# HP85disk.net
KiCad netlist of a schematic drawn in EAGLE
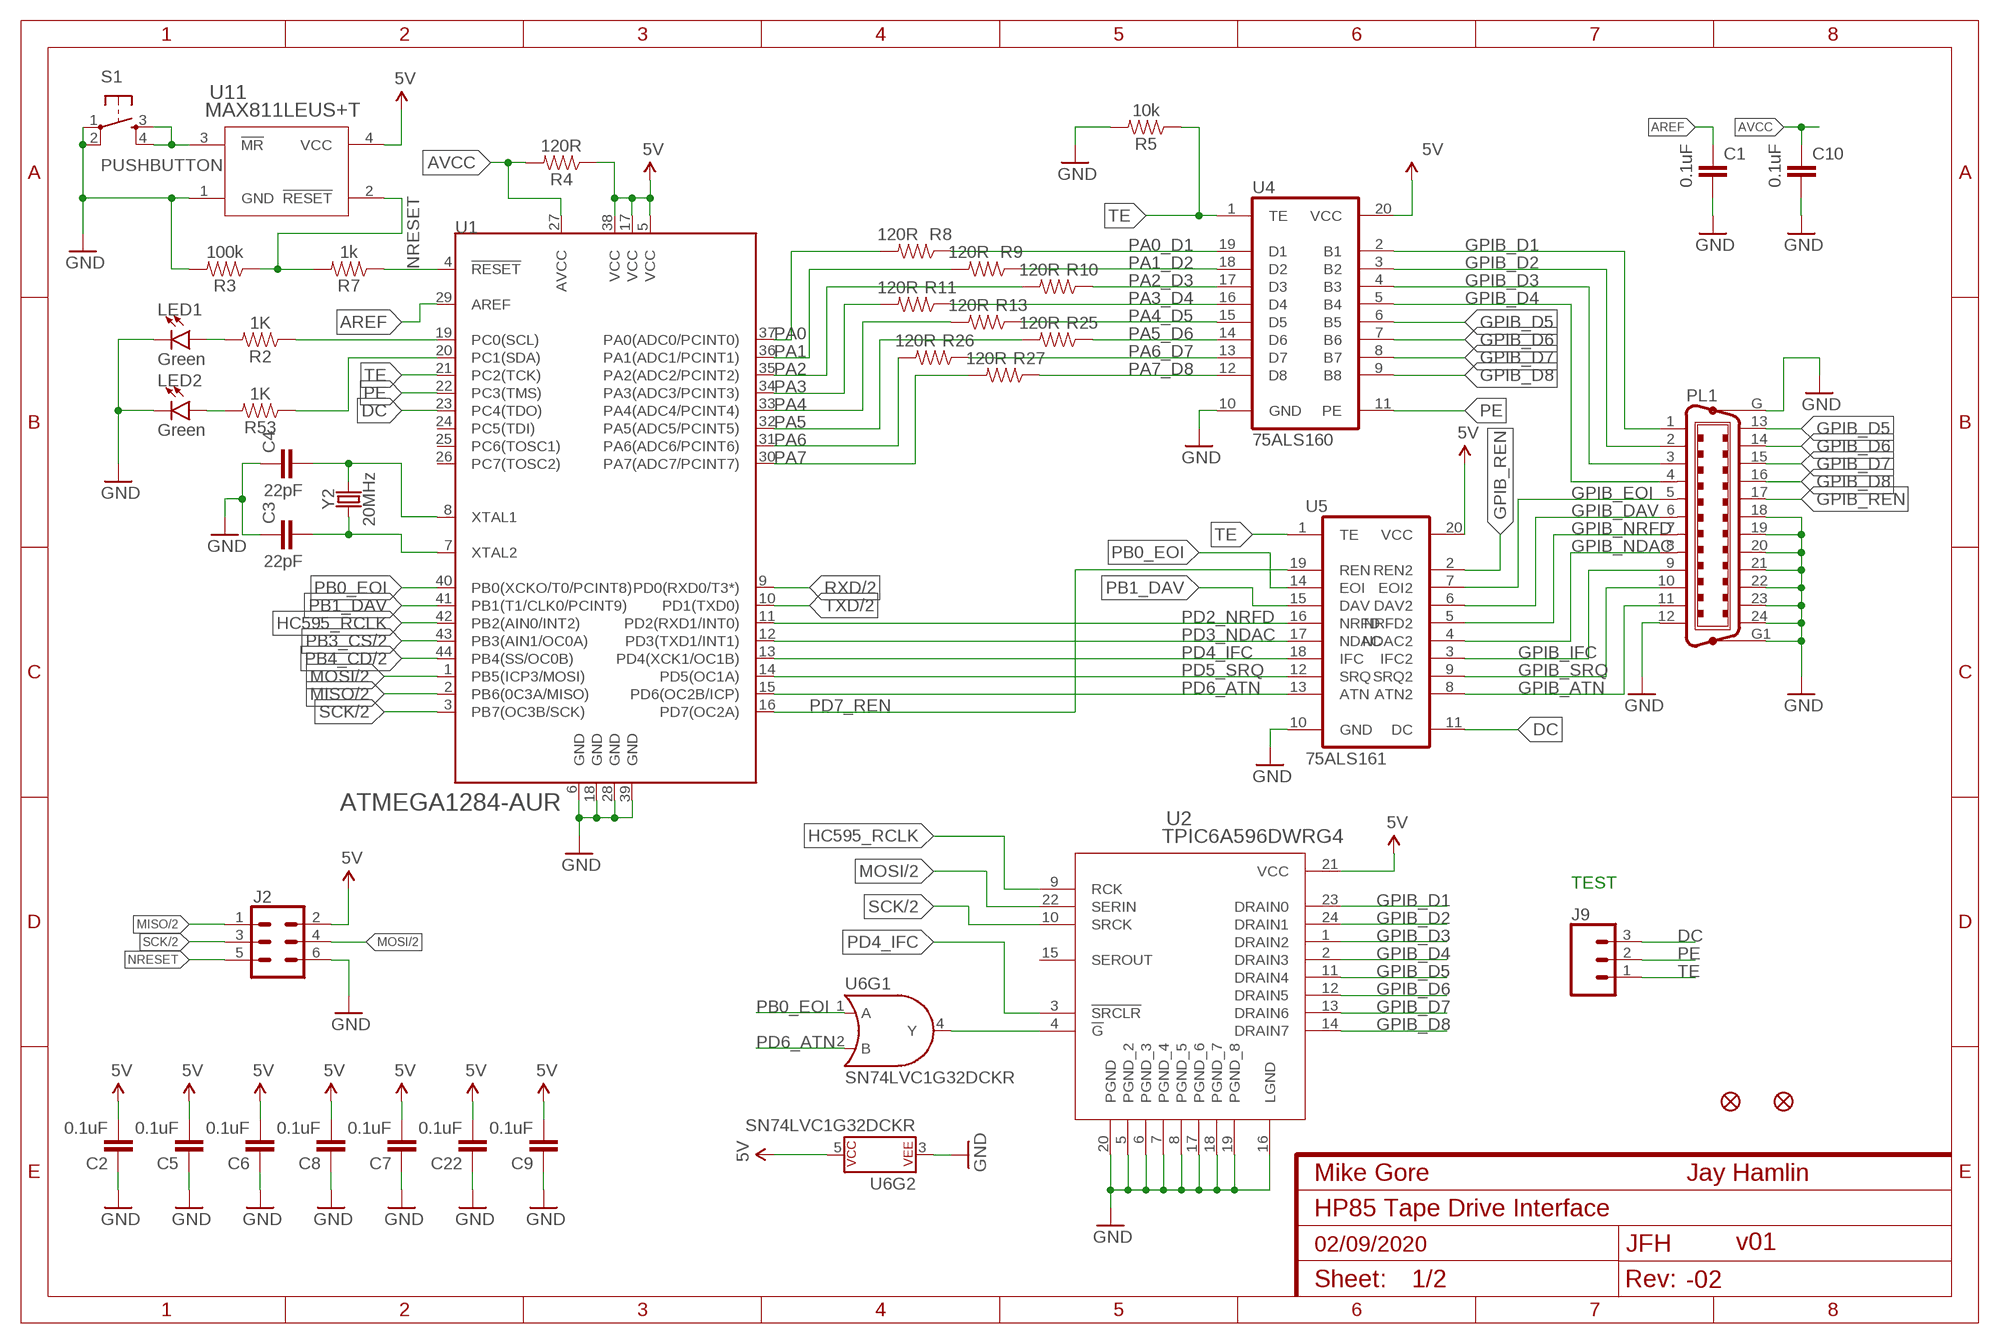
[diagram p0: schematic, sheet 1]
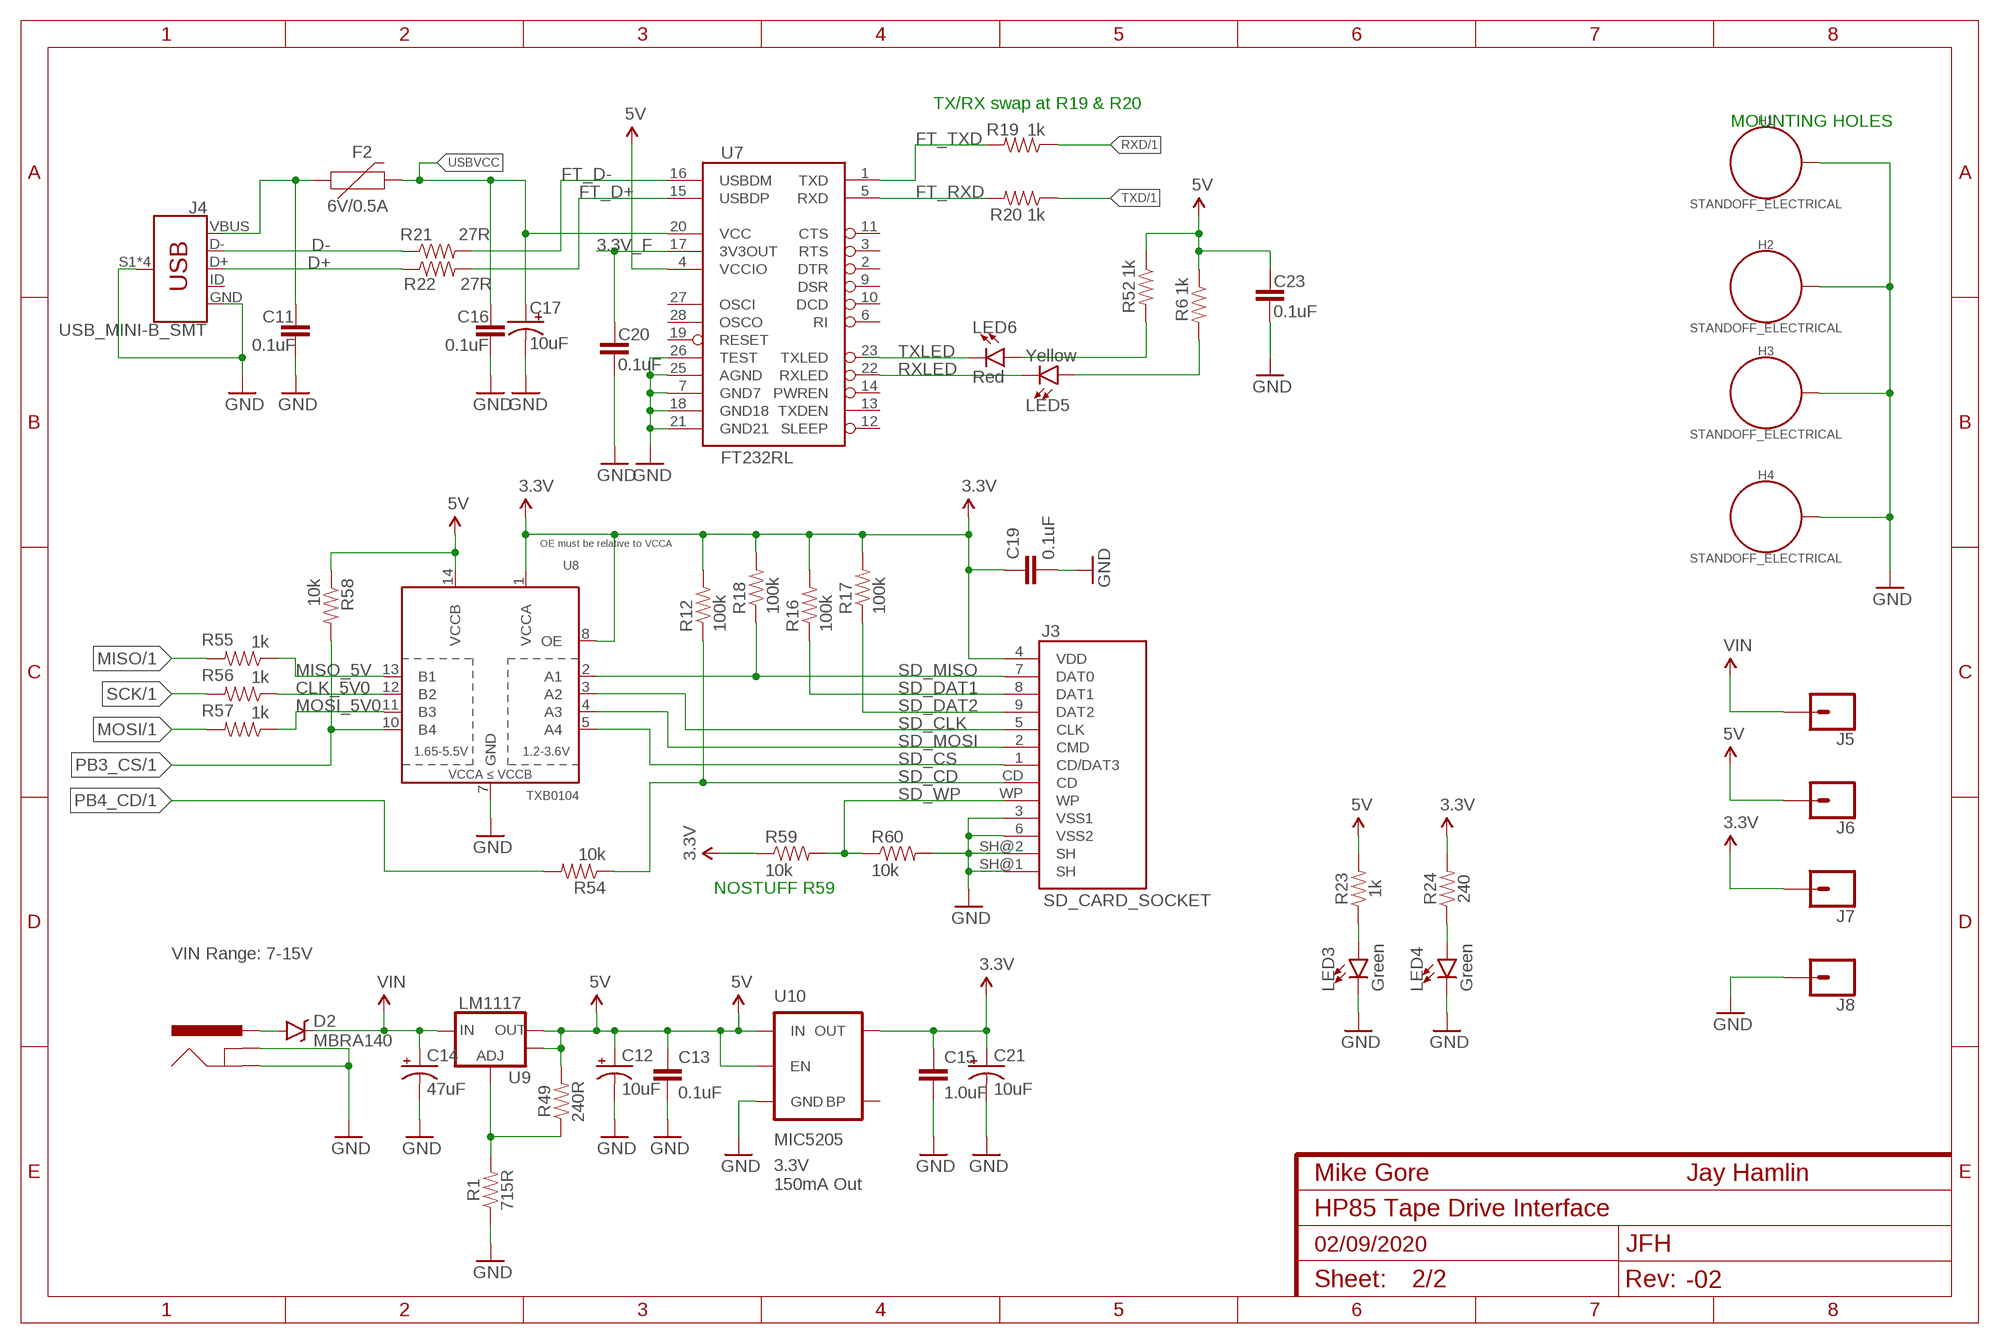
[diagram p1: schematic, sheet 2]

(export (version "E")
  (design (tool "Eeschema 10.0.6"))
  (components
    (comp (ref "C11")
      (value "0.1uF")
      (footprint "eagle-import:0603")
      (libsource (lib "eagle-import") (part "0.1UF-0603-25V-(+80/-20%)"))
    )
    (comp (ref "C12")
      (value "10uF")
      (footprint "eagle-import:EIA3216")
      (libsource (lib "eagle-import") (part "10UF-POLAR-EIA3216-16V-10%(TANT)"))
    )
    (comp (ref "C13")
      (value "0.1uF")
      (footprint "eagle-import:0603")
      (libsource (lib "eagle-import") (part "0.1UF-0603-25V-(+80/-20%)"))
    )
    (comp (ref "C14")
      (value "47uF")
      (footprint "eagle-import:PANASONIC_D")
      (libsource (lib "eagle-import") (part "47UF-POLAR-PANASONIC_D-35V-20%"))
    )
    (comp (ref "C15")
      (value "1.0uF")
      (footprint "eagle-import:0603")
      (libsource (lib "eagle-import") (part "1.0UF-0603-16V-10%"))
    )
    (comp (ref "C16")
      (value "0.1uF")
      (footprint "eagle-import:0603")
      (libsource (lib "eagle-import") (part "0.1UF-0603-25V-(+80/-20%)"))
    )
    (comp (ref "C17")
      (value "10uF")
      (footprint "eagle-import:EIA3216")
      (libsource (lib "eagle-import") (part "10UF-POLAR-EIA3216-16V-10%(TANT)"))
    )
    (comp (ref "C19")
      (value "0.1uF")
      (footprint "eagle-import:0603")
      (libsource (lib "eagle-import") (part "0.1UF-0603-25V-(+80/-20%)"))
    )
    (comp (ref "C20")
      (value "0.1uF")
      (footprint "eagle-import:0603")
      (libsource (lib "eagle-import") (part "0.1UF-0603-25V-(+80/-20%)"))
    )
    (comp (ref "C21")
      (value "10uF")
      (footprint "eagle-import:EIA3216")
      (libsource (lib "eagle-import") (part "10UF-POLAR-EIA3216-16V-10%(TANT)"))
    )
    (comp (ref "C23")
      (value "0.1uF")
      (footprint "eagle-import:0603")
      (libsource (lib "eagle-import") (part "0.1UF-0603-25V-(+80/-20%)"))
    )
    (comp (ref "D2")
      (value "MBRA140")
      (footprint "eagle-import:SMA-DIODE")
      (libsource (lib "eagle-import") (part "MBRA140"))
    )
    (comp (ref "F2")
      (value "6V/0.5A")
      (footprint "eagle-import:1206")
      (libsource (lib "eagle-import") (part "PTC-HALF_AMP"))
    )
    (comp (ref "H1")
      (value "STANDOFF_ELECTRICAL")
      (footprint "eagle-import:STANDOFF-ELECTRICAL")
      (libsource (lib "eagle-import") (part "STANDOFF_ELECTRICAL"))
    )
    (comp (ref "H2")
      (value "STANDOFF_ELECTRICAL")
      (footprint "eagle-import:STANDOFF-ELECTRICAL")
      (libsource (lib "eagle-import") (part "STANDOFF_ELECTRICAL"))
    )
    (comp (ref "H3")
      (value "STANDOFF_ELECTRICAL")
      (footprint "eagle-import:STANDOFF-ELECTRICAL")
      (libsource (lib "eagle-import") (part "STANDOFF_ELECTRICAL"))
    )
    (comp (ref "H4")
      (value "STANDOFF_ELECTRICAL")
      (footprint "eagle-import:STANDOFF-ELECTRICAL")
      (libsource (lib "eagle-import") (part "STANDOFF_ELECTRICAL"))
    )
    (comp (ref "J1")
      (value "POWER_JACKSUPER_BOMB_DIGITY")
      (footprint "eagle-import:POWER_JACK_SMD_OVERPASTE_SUPER_BOMB_DIGITY")
      (libsource (lib "eagle-import") (part "POWER_JACKSUPER_BOMB_DIGITY"))
    )
    (comp (ref "J3")
      (value "SD_CARD_SOCKET")
      (footprint "eagle-import:SD_1_1")
      (libsource (lib "eagle-import") (part "SD_CARD_SOCKET"))
    )
    (comp (ref "J4")
      (value "USB_MINI-B_SMT")
      (footprint "eagle-import:USB-MINIB")
      (libsource (lib "eagle-import") (part "USB_MINI-B_SMT"))
    )
    (comp (ref "J5")
      (value "CONN_01")
      (footprint "eagle-import:1X01")
      (libsource (lib "eagle-import") (part "CONN_01"))
    )
    (comp (ref "J6")
      (value "CONN_01")
      (footprint "eagle-import:1X01")
      (libsource (lib "eagle-import") (part "CONN_01"))
    )
    (comp (ref "J7")
      (value "CONN_01")
      (footprint "eagle-import:1X01")
      (libsource (lib "eagle-import") (part "CONN_01"))
    )
    (comp (ref "J8")
      (value "CONN_01")
      (footprint "eagle-import:1X01")
      (libsource (lib "eagle-import") (part "CONN_01"))
    )
    (comp (ref "LED3")
      (value "Green")
      (footprint "eagle-import:LED-1206")
      (libsource (lib "eagle-import") (part "LED1206"))
    )
    (comp (ref "LED4")
      (value "Green")
      (footprint "eagle-import:LED-1206")
      (libsource (lib "eagle-import") (part "LED1206"))
    )
    (comp (ref "LED5")
      (value "Yellow")
      (footprint "eagle-import:LED-1206")
      (libsource (lib "eagle-import") (part "LED1206"))
    )
    (comp (ref "LED6")
      (value "Red")
      (footprint "eagle-import:LED-1206")
      (libsource (lib "eagle-import") (part "LED1206"))
    )
    (comp (ref "R1")
      (value "715R")
      (footprint "eagle-import:0603")
      (libsource (lib "eagle-import") (part "715OHM-0603-1/10W-1%"))
    )
    (comp (ref "R6")
      (value "1k")
      (footprint "eagle-import:0603")
      (libsource (lib "eagle-import") (part "1KOHM-0603-1/10W-1%"))
    )
    (comp (ref "R12")
      (value "100k")
      (footprint "eagle-import:0603-RES")
      (libsource (lib "eagle-import") (part "100KOHM-1/10W-1%(0603)"))
    )
    (comp (ref "R16")
      (value "100k")
      (footprint "eagle-import:0603-RES")
      (libsource (lib "eagle-import") (part "100KOHM-1/10W-1%(0603)"))
    )
    (comp (ref "R17")
      (value "100k")
      (footprint "eagle-import:0603-RES")
      (libsource (lib "eagle-import") (part "100KOHM-1/10W-1%(0603)"))
    )
    (comp (ref "R18")
      (value "100k")
      (footprint "eagle-import:0603-RES")
      (libsource (lib "eagle-import") (part "100KOHM-1/10W-1%(0603)"))
    )
    (comp (ref "R19")
      (value "1k")
      (footprint "eagle-import:0603")
      (libsource (lib "eagle-import") (part "1KOHM-0603-1/10W-1%"))
    )
    (comp (ref "R20")
      (value "1k")
      (footprint "eagle-import:0603")
      (libsource (lib "eagle-import") (part "1KOHM-0603-1/10W-1%"))
    )
    (comp (ref "R21")
      (value "27R")
      (footprint "eagle-import:0603")
      (libsource (lib "eagle-import") (part "27OHM-0603-1/10W-1%"))
    )
    (comp (ref "R22")
      (value "27R")
      (footprint "eagle-import:0603")
      (libsource (lib "eagle-import") (part "27OHM-0603-1/10W-1%"))
    )
    (comp (ref "R23")
      (value "1k")
      (footprint "eagle-import:0603")
      (libsource (lib "eagle-import") (part "4.7KOHM-0603-1/10W-1%"))
    )
    (comp (ref "R24")
      (value "240")
      (footprint "eagle-import:0603")
      (libsource (lib "eagle-import") (part "4.7KOHM-0603-1/10W-1%"))
    )
    (comp (ref "R49")
      (value "240R")
      (footprint "eagle-import:0603")
      (libsource (lib "eagle-import") (part "240OHM-0603-1/10W-1%"))
    )
    (comp (ref "R52")
      (value "1k")
      (footprint "eagle-import:0603")
      (libsource (lib "eagle-import") (part "1KOHM-0603-1/10W-1%"))
    )
    (comp (ref "R54")
      (value "10k")
      (footprint "eagle-import:0603-RES")
      (libsource (lib "eagle-import") (part "100KOHM-1/10W-1%(0603)"))
    )
    (comp (ref "R55")
      (value "1k")
      (footprint "eagle-import:0603-RES")
      (libsource (lib "eagle-import") (part "100KOHM-1/10W-1%(0603)"))
    )
    (comp (ref "R56")
      (value "1k")
      (footprint "eagle-import:0603-RES")
      (libsource (lib "eagle-import") (part "100KOHM-1/10W-1%(0603)"))
    )
    (comp (ref "R57")
      (value "1k")
      (footprint "eagle-import:0603-RES")
      (libsource (lib "eagle-import") (part "100KOHM-1/10W-1%(0603)"))
    )
    (comp (ref "R58")
      (value "10k")
      (footprint "eagle-import:0603-RES")
      (libsource (lib "eagle-import") (part "100KOHM-1/10W-1%(0603)"))
    )
    (comp (ref "R59")
      (value "10k")
      (footprint "eagle-import:0603-RES")
      (libsource (lib "eagle-import") (part "100KOHM-1/10W-1%(0603)"))
    )
    (comp (ref "R60")
      (value "10k")
      (footprint "eagle-import:0603-RES")
      (libsource (lib "eagle-import") (part "100KOHM-1/10W-1%(0603)"))
    )
    (comp (ref "U7")
      (value "FT232RL")
      (footprint "eagle-import:SSOP28DB")
      (libsource (lib "eagle-import") (part "FT232RLSSOP"))
    )
    (comp (ref "U8")
      (value "TXB0104")
      (footprint "eagle-import:SO14")
      (libsource (lib "eagle-import") (part "TXB0104PWRSOIC14"))
    )
    (comp (ref "U9")
      (value "LM1117")
      (footprint "eagle-import:SOT223-ALT1")
      (libsource (lib "eagle-import") (part "V_REG_LM1117ALT1"))
    )
    (comp (ref "U10")
      (value "MIC5205")
      (footprint "eagle-import:SOT23-5")
      (libsource (lib "eagle-import") (part "MIC52053.3V"))
    )
    (comp (ref "C1")
      (value "0.1uF")
      (footprint "eagle-import:0603")
      (libsource (lib "eagle-import") (part "0.1UF-0603-25V-(+80/-20%)"))
    )
    (comp (ref "C2")
      (value "0.1uF")
      (footprint "eagle-import:0603")
      (fields (field (name "SPICEPREFIX") "C"))
      (libsource (lib "eagle-import") (part "0.1UF-0603-25V-(+80/-20%)"))
    )
    (comp (ref "C3")
      (value "22pF")
      (footprint "eagle-import:0603")
      (libsource (lib "eagle-import") (part "0.1UF-0603-25V-(+80/-20%)"))
    )
    (comp (ref "C4")
      (value "22pF")
      (footprint "eagle-import:0603")
      (libsource (lib "eagle-import") (part "0.1UF-0603-25V-(+80/-20%)"))
    )
    (comp (ref "C5")
      (value "0.1uF")
      (footprint "eagle-import:0603")
      (fields (field (name "SPICEPREFIX") "C"))
      (libsource (lib "eagle-import") (part "0.1UF-0603-25V-(+80/-20%)"))
    )
    (comp (ref "C6")
      (value "0.1uF")
      (footprint "eagle-import:0603")
      (fields (field (name "SPICEPREFIX") "C"))
      (libsource (lib "eagle-import") (part "0.1UF-0603-25V-(+80/-20%)"))
    )
    (comp (ref "C7")
      (value "0.1uF")
      (footprint "eagle-import:0603")
      (fields (field (name "SPICEPREFIX") "C"))
      (libsource (lib "eagle-import") (part "0.1UF-0603-25V-(+80/-20%)"))
    )
    (comp (ref "C8")
      (value "0.1uF")
      (footprint "eagle-import:0603")
      (fields (field (name "SPICEPREFIX") "C"))
      (libsource (lib "eagle-import") (part "0.1UF-0603-25V-(+80/-20%)"))
    )
    (comp (ref "C9")
      (value "0.1uF")
      (footprint "eagle-import:0603")
      (libsource (lib "eagle-import") (part "0.1UF-0603-25V-(+80/-20%)"))
    )
    (comp (ref "C10")
      (value "0.1uF")
      (footprint "eagle-import:0603")
      (libsource (lib "eagle-import") (part "0.1UF-0603-25V-(+80/-20%)"))
    )
    (comp (ref "C22")
      (value "0.1uF")
      (footprint "eagle-import:0603")
      (libsource (lib "eagle-import") (part "0.1UF-0603-25V-(+80/-20%)"))
    )
    (comp (ref "J2")
      (value "CONN_03X2_BIGPADSFEMALE_SMD")
      (footprint "eagle-import:2X3_SMD")
      (libsource (lib "eagle-import") (part "CONN_03X2_BIGPADSFEMALE_SMD"))
    )
    (comp (ref "J9")
      (value "CONN_03")
      (footprint "eagle-import:1X03")
      (libsource (lib "eagle-import") (part "CONN_03"))
    )
    (comp (ref "JP8")
      (value "FIDUCIAL1X2")
      (footprint "eagle-import:FIDUCIAL-1X2")
      (libsource (lib "eagle-import") (part "FIDUCIAL1X2"))
    )
    (comp (ref "JP9")
      (value "FIDUCIAL1X2")
      (footprint "eagle-import:FIDUCIAL-1X2")
      (libsource (lib "eagle-import") (part "FIDUCIAL1X2"))
    )
    (comp (ref "LED1")
      (value "Green")
      (footprint "eagle-import:LED-1206")
      (libsource (lib "eagle-import") (part "LED1206"))
    )
    (comp (ref "LED2")
      (value "Green")
      (footprint "eagle-import:LED-1206")
      (libsource (lib "eagle-import") (part "LED1206"))
    )
    (comp (ref "PL1")
      (value "C24HP")
      (footprint "eagle-import:24HP")
      (libsource (lib "eagle-import") (part "C24HP"))
    )
    (comp (ref "R2")
      (value "1K")
      (footprint "eagle-import:0603")
      (libsource (lib "eagle-import") (part "4.7KOHM-0603-1/10W-1%"))
    )
    (comp (ref "R3")
      (value "100k")
      (footprint "eagle-import:0603")
      (libsource (lib "eagle-import") (part "10KOHM-0603-1/10W-1%"))
    )
    (comp (ref "R4")
      (value "120R")
      (footprint "eagle-import:0603")
      (libsource (lib "eagle-import") (part "10KOHM-0603-1/10W-1%"))
    )
    (comp (ref "R5")
      (value "10k")
      (footprint "eagle-import:0603")
      (libsource (lib "eagle-import") (part "10KOHM-0603-1/10W-1%"))
    )
    (comp (ref "R7")
      (value "1k")
      (footprint "eagle-import:0603")
      (libsource (lib "eagle-import") (part "10KOHM-0603-1/10W-1%"))
    )
    (comp (ref "R8")
      (value "120R")
      (footprint "eagle-import:0603")
      (libsource (lib "eagle-import") (part "10KOHM-0603-1/10W-1%"))
    )
    (comp (ref "R9")
      (value "120R")
      (footprint "eagle-import:0603")
      (libsource (lib "eagle-import") (part "10KOHM-0603-1/10W-1%"))
    )
    (comp (ref "R10")
      (value "120R")
      (footprint "eagle-import:0603")
      (libsource (lib "eagle-import") (part "10KOHM-0603-1/10W-1%"))
    )
    (comp (ref "R11")
      (value "120R")
      (footprint "eagle-import:0603")
      (libsource (lib "eagle-import") (part "10KOHM-0603-1/10W-1%"))
    )
    (comp (ref "R13")
      (value "120R")
      (footprint "eagle-import:0603")
      (libsource (lib "eagle-import") (part "10KOHM-0603-1/10W-1%"))
    )
    (comp (ref "R25")
      (value "120R")
      (footprint "eagle-import:0603")
      (libsource (lib "eagle-import") (part "10KOHM-0603-1/10W-1%"))
    )
    (comp (ref "R26")
      (value "120R")
      (footprint "eagle-import:0603")
      (libsource (lib "eagle-import") (part "10KOHM-0603-1/10W-1%"))
    )
    (comp (ref "R27")
      (value "120R")
      (footprint "eagle-import:0603")
      (libsource (lib "eagle-import") (part "10KOHM-0603-1/10W-1%"))
    )
    (comp (ref "R53")
      (value "1K")
      (footprint "eagle-import:0603")
      (libsource (lib "eagle-import") (part "4.7KOHM-0603-1/10W-1%"))
    )
    (comp (ref "S1")
      (value "PUSHBUTTON")
      (footprint "eagle-import:TACTILE-SWITCH-SMD")
      (libsource (lib "eagle-import") (part "SWITCH_SPST_4_PINSQUARE"))
    )
    (comp (ref "U1")
      (value "ATMEGA1284-AUR")
      (footprint "eagle-import:TQFP44")
      (libsource (lib "eagle-import") (part "ATMEGA1284AUTQFP-44"))
    )
    (comp (ref "U2")
      (value "TPIC6A596DWRG4")
      (footprint "eagle-import:DW24")
      (fields (field (name "MANUFACTURER") "Texas Instruments"))
      (libsource (lib "eagle-import") (part "TPIC6A596DWRG4"))
    )
    (comp (ref "U4")
      (value "75ALS160")
      (footprint "eagle-import:SO20L")
      (libsource (lib "eagle-import") (part "75160SO"))
    )
    (comp (ref "U5")
      (value "75ALS161")
      (footprint "eagle-import:SO20L")
      (libsource (lib "eagle-import") (part "75161SO"))
    )
    (comp (ref "U6")
      (value "SN74LVC1G32DCKR")
      (footprint "eagle-import:SOT23-5")
      (libsource (lib "eagle-import") (part "7432DBVLVC"))
    )
    (comp (ref "U11")
      (value "MAX811LEUS+T")
      (footprint "eagle-import:21-0052F")
      (fields
        (field (name "MANUFACTURER_PART_NUMBER") "MAX811TEUS+T")
        (field (name "COPYRIGHT") "Copyright (C) 2018 Accelerated Designs. All rights reserved")
      )
      (libsource (lib "eagle-import") (part "MAX811TEUS+T"))
    )
    (comp (ref "Y2")
      (value "20MHz")
      (footprint "eagle-import:CRYSTAL-SMD-5X3.2-4PAD")
      (libsource (lib "eagle-import") (part "CRYSTAL-16MHZSMD-5X3.2"))
    )
  )
  (nets
    (net (code "1") (name "3.3V") (class "Default")
      (node (ref "C15") (pin "1") (pinfunction "1_1") (pintype "passive"))
      (node (ref "C19") (pin "1") (pinfunction "1_1") (pintype "passive"))
      (node (ref "C21") (pin "+") (pinfunction "+_+") (pintype "passive"))
      (node (ref "J3") (pin "4") (pinfunction "VDD_4") (pintype "power_in"))
      (node (ref "J7") (pin "1") (pinfunction "1_1") (pintype "passive"))
      (node (ref "R12") (pin "2") (pinfunction "2_2") (pintype "passive"))
      (node (ref "R16") (pin "2") (pinfunction "2_2") (pintype "passive"))
      (node (ref "R17") (pin "2") (pinfunction "2_2") (pintype "passive"))
      (node (ref "R18") (pin "2") (pinfunction "2_2") (pintype "passive"))
      (node (ref "R24") (pin "2") (pinfunction "2_2") (pintype "passive"))
      (node (ref "R59") (pin "1") (pinfunction "1_1") (pintype "passive"))
      (node (ref "U10") (pin "5") (pinfunction "OUT_5") (pintype "passive"))
      (node (ref "U8") (pin "1") (pinfunction "VCCA_1") (pintype "bidirectional"))
      (node (ref "U8") (pin "8") (pinfunction "OE_8") (pintype "bidirectional"))
    )
    (net (code "2") (name "3.3V_F") (class "Default")
      (node (ref "C20") (pin "1") (pinfunction "1_1") (pintype "passive"))
      (node (ref "U7") (pin "17") (pinfunction "3V3OUT_17") (pintype "output"))
    )
    (net (code "3") (name "5V") (class "Default")
      (node (ref "C12") (pin "+") (pinfunction "+_+") (pintype "passive"))
      (node (ref "C13") (pin "1") (pinfunction "1_1") (pintype "passive"))
      (node (ref "C2") (pin "2") (pinfunction "2_2") (pintype "passive"))
      (node (ref "C22") (pin "2") (pinfunction "2_2") (pintype "passive"))
      (node (ref "C23") (pin "1") (pinfunction "1_1") (pintype "passive"))
      (node (ref "C5") (pin "2") (pinfunction "2_2") (pintype "passive"))
      (node (ref "C6") (pin "2") (pinfunction "2_2") (pintype "passive"))
      (node (ref "C7") (pin "2") (pinfunction "2_2") (pintype "passive"))
      (node (ref "C8") (pin "2") (pinfunction "2_2") (pintype "passive"))
      (node (ref "C9") (pin "2") (pinfunction "2_2") (pintype "passive"))
      (node (ref "J2") (pin "2") (pinfunction "2_2") (pintype "bidirectional"))
      (node (ref "J6") (pin "1") (pinfunction "1_1") (pintype "passive"))
      (node (ref "R23") (pin "2") (pinfunction "2_2") (pintype "passive"))
      (node (ref "R4") (pin "1") (pinfunction "1_1") (pintype "passive"))
      (node (ref "R49") (pin "2") (pinfunction "2_2") (pintype "passive"))
      (node (ref "R52") (pin "1") (pinfunction "1_1") (pintype "passive"))
      (node (ref "R58") (pin "1") (pinfunction "1_1") (pintype "passive"))
      (node (ref "R6") (pin "1") (pinfunction "1_1") (pintype "passive"))
      (node (ref "U1") (pin "17") (pinfunction "VCC_17") (pintype "bidirectional"))
      (node (ref "U1") (pin "38") (pinfunction "VCC_38") (pintype "bidirectional"))
      (node (ref "U1") (pin "5") (pinfunction "VCC_5") (pintype "bidirectional"))
      (node (ref "U10") (pin "1") (pinfunction "IN_1") (pintype "input"))
      (node (ref "U10") (pin "3") (pinfunction "EN_3") (pintype "input"))
      (node (ref "U11") (pin "4") (pinfunction "VCC_4") (pintype "power_in"))
      (node (ref "U2") (pin "21") (pinfunction "VCC_21") (pintype "power_in"))
      (node (ref "U4") (pin "20") (pinfunction "VCC_20") (pintype "bidirectional"))
      (node (ref "U5") (pin "20") (pinfunction "VCC_20") (pintype "bidirectional"))
      (node (ref "U6") (pin "5") (pinfunction "P$V+_5") (pintype "bidirectional"))
      (node (ref "U7") (pin "4") (pinfunction "VCCIO_4") (pintype "power_in"))
      (node (ref "U8") (pin "14") (pinfunction "VCCB_14") (pintype "bidirectional"))
      (node (ref "U9") (pin "2") (pinfunction "OUT_2") (pintype "output"))
      (node (ref "U9") (pin "4") (pinfunction "OUT_4") (pintype "output"))
    )
    (net (code "4") (name "AREF") (class "Default")
      (node (ref "C1") (pin "1") (pinfunction "1_1") (pintype "passive"))
      (node (ref "U1") (pin "29") (pinfunction "AREF_29") (pintype "bidirectional"))
    )
    (net (code "5") (name "AVCC") (class "Default")
      (node (ref "C10") (pin "1") (pinfunction "1_1") (pintype "passive"))
      (node (ref "R4") (pin "2") (pinfunction "2_2") (pintype "passive"))
      (node (ref "U1") (pin "27") (pinfunction "AVCC_27") (pintype "bidirectional"))
    )
    (net (code "6") (name "CLK_5V0") (class "Default")
      (node (ref "R56") (pin "1") (pinfunction "1_1") (pintype "passive"))
      (node (ref "U8") (pin "12") (pinfunction "B2_12") (pintype "bidirectional"))
    )
    (net (code "7") (name "D+") (class "Default")
      (node (ref "J4") (pin "D+") (pinfunction "D+_D+") (pintype "bidirectional"))
      (node (ref "R22") (pin "1") (pinfunction "1_1") (pintype "passive"))
    )
    (net (code "8") (name "D-") (class "Default")
      (node (ref "J4") (pin "D-") (pinfunction "D-_D-") (pintype "bidirectional"))
      (node (ref "R21") (pin "1") (pinfunction "1_1") (pintype "passive"))
    )
    (net (code "9") (name "DC") (class "Default")
      (node (ref "J9") (pin "3") (pinfunction "3_3") (pintype "passive"))
      (node (ref "U1") (pin "23") (pinfunction "PC4(TDO)_23") (pintype "bidirectional"))
      (node (ref "U5") (pin "11") (pinfunction "DC_11") (pintype "input"))
    )
    (net (code "10") (name "FT_D+") (class "Default")
      (node (ref "R22") (pin "2") (pinfunction "2_2") (pintype "passive"))
      (node (ref "U7") (pin "15") (pinfunction "USBDP_15") (pintype "bidirectional"))
    )
    (net (code "11") (name "FT_D-") (class "Default")
      (node (ref "R21") (pin "2") (pinfunction "2_2") (pintype "passive"))
      (node (ref "U7") (pin "16") (pinfunction "USBDM_16") (pintype "bidirectional"))
    )
    (net (code "12") (name "FT_RXD") (class "Default")
      (node (ref "R20") (pin "2") (pinfunction "2_2") (pintype "passive"))
      (node (ref "U7") (pin "5") (pinfunction "RXD_5") (pintype "input"))
    )
    (net (code "13") (name "FT_TXD") (class "Default")
      (node (ref "R19") (pin "2") (pinfunction "2_2") (pintype "passive"))
      (node (ref "U7") (pin "1") (pinfunction "TXD_1") (pintype "output"))
    )
    (net (code "14") (name "GND") (class "Default")
      (node (ref "C1") (pin "2") (pinfunction "2_2") (pintype "passive"))
      (node (ref "C10") (pin "2") (pinfunction "2_2") (pintype "passive"))
      (node (ref "C11") (pin "2") (pinfunction "2_2") (pintype "passive"))
      (node (ref "C12") (pin "-") (pinfunction "-_-") (pintype "passive"))
      (node (ref "C13") (pin "2") (pinfunction "2_2") (pintype "passive"))
      (node (ref "C14") (pin "-") (pinfunction "-_-") (pintype "passive"))
      (node (ref "C15") (pin "2") (pinfunction "2_2") (pintype "passive"))
      (node (ref "C16") (pin "2") (pinfunction "2_2") (pintype "passive"))
      (node (ref "C17") (pin "-") (pinfunction "-_-") (pintype "passive"))
      (node (ref "C19") (pin "2") (pinfunction "2_2") (pintype "passive"))
      (node (ref "C2") (pin "1") (pinfunction "1_1") (pintype "passive"))
      (node (ref "C20") (pin "2") (pinfunction "2_2") (pintype "passive"))
      (node (ref "C21") (pin "-") (pinfunction "-_-") (pintype "passive"))
      (node (ref "C22") (pin "1") (pinfunction "1_1") (pintype "passive"))
      (node (ref "C23") (pin "2") (pinfunction "2_2") (pintype "passive"))
      (node (ref "C3") (pin "1") (pinfunction "1_1") (pintype "passive"))
      (node (ref "C4") (pin "1") (pinfunction "1_1") (pintype "passive"))
      (node (ref "C5") (pin "1") (pinfunction "1_1") (pintype "passive"))
      (node (ref "C6") (pin "1") (pinfunction "1_1") (pintype "passive"))
      (node (ref "C7") (pin "1") (pinfunction "1_1") (pintype "passive"))
      (node (ref "C8") (pin "1") (pinfunction "1_1") (pintype "passive"))
      (node (ref "C9") (pin "1") (pinfunction "1_1") (pintype "passive"))
      (node (ref "H1") (pin "P1") (pinfunction "P$1_P1") (pintype "bidirectional"))
      (node (ref "H2") (pin "P1") (pinfunction "P$1_P1") (pintype "bidirectional"))
      (node (ref "H3") (pin "P1") (pinfunction "P$1_P1") (pintype "bidirectional"))
      (node (ref "H4") (pin "P1") (pinfunction "P$1_P1") (pintype "bidirectional"))
      (node (ref "J1") (pin "GND") (pinfunction "GNDBREAK_GND") (pintype "bidirectional"))
      (node (ref "J1") (pin "P$4") (pinfunction "GND_P$4") (pintype "bidirectional"))
      (node (ref "J2") (pin "6") (pinfunction "6_6") (pintype "bidirectional"))
      (node (ref "J3") (pin "3") (pinfunction "VSS1_3") (pintype "power_in"))
      (node (ref "J3") (pin "6") (pinfunction "VSS2_6") (pintype "power_in"))
      (node (ref "J3") (pin "SH@1") (pinfunction "SH_SH@1") (pintype "bidirectional"))
      (node (ref "J3") (pin "SH@2") (pinfunction "SH_SH@2") (pintype "bidirectional"))
      (node (ref "J4") (pin "GND") (pinfunction "GND_GND") (pintype "power_in"))
      (node (ref "J4") (pin "S1") (pinfunction "SHIELD_S1") (pintype "bidirectional"))
      (node (ref "J4") (pin "S2") (pinfunction "SHIELD_S2") (pintype "bidirectional"))
      (node (ref "J4") (pin "S3") (pinfunction "SHIELD_S3") (pintype "bidirectional"))
      (node (ref "J4") (pin "S4") (pinfunction "SHIELD_S4") (pintype "bidirectional"))
      (node (ref "J8") (pin "1") (pinfunction "1_1") (pintype "passive"))
      (node (ref "LED1") (pin "C") (pinfunction "C_C") (pintype "passive"))
      (node (ref "LED2") (pin "C") (pinfunction "C_C") (pintype "passive"))
      (node (ref "LED3") (pin "C") (pinfunction "C_C") (pintype "passive"))
      (node (ref "LED4") (pin "C") (pinfunction "C_C") (pintype "passive"))
      (node (ref "PL1") (pin "12") (pinfunction "12_12") (pintype "passive"))
      (node (ref "PL1") (pin "18") (pinfunction "18_18") (pintype "passive"))
      (node (ref "PL1") (pin "19") (pinfunction "19_19") (pintype "passive"))
      (node (ref "PL1") (pin "20") (pinfunction "20_20") (pintype "passive"))
      (node (ref "PL1") (pin "21") (pinfunction "21_21") (pintype "passive"))
      (node (ref "PL1") (pin "22") (pinfunction "22_22") (pintype "passive"))
      (node (ref "PL1") (pin "23") (pinfunction "23_23") (pintype "passive"))
      (node (ref "PL1") (pin "24") (pinfunction "24_24") (pintype "passive"))
      (node (ref "PL1") (pin "G") (pinfunction "G_G") (pintype "passive"))
      (node (ref "PL1") (pin "G1") (pinfunction "G1_G1") (pintype "passive"))
      (node (ref "R1") (pin "1") (pinfunction "1_1") (pintype "passive"))
      (node (ref "R3") (pin "2") (pinfunction "2_2") (pintype "passive"))
      (node (ref "R5") (pin "2") (pinfunction "2_2") (pintype "passive"))
      (node (ref "R60") (pin "2") (pinfunction "2_2") (pintype "passive"))
      (node (ref "S1") (pin "1") (pinfunction "1_1") (pintype "passive"))
      (node (ref "S1") (pin "2") (pinfunction "2_2") (pintype "passive"))
      (node (ref "U1") (pin "18") (pinfunction "GND_18") (pintype "bidirectional"))
      (node (ref "U1") (pin "28") (pinfunction "GND_28") (pintype "bidirectional"))
      (node (ref "U1") (pin "39") (pinfunction "GND_39") (pintype "bidirectional"))
      (node (ref "U1") (pin "6") (pinfunction "GND_6") (pintype "bidirectional"))
      (node (ref "U10") (pin "2") (pinfunction "GND_2") (pintype "input"))
      (node (ref "U11") (pin "1") (pinfunction "GND_1") (pintype "power_in"))
      (node (ref "U2") (pin "16") (pinfunction "LGND_16") (pintype "power_in"))
      (node (ref "U2") (pin "17") (pinfunction "PGND_6_17") (pintype "power_in"))
      (node (ref "U2") (pin "18") (pinfunction "PGND_7_18") (pintype "power_in"))
      (node (ref "U2") (pin "19") (pinfunction "PGND_8_19") (pintype "power_in"))
      (node (ref "U2") (pin "20") (pinfunction "PGND_20") (pintype "power_in"))
      (node (ref "U2") (pin "5") (pinfunction "PGND_2_5") (pintype "power_in"))
      (node (ref "U2") (pin "6") (pinfunction "PGND_3_6") (pintype "power_in"))
      (node (ref "U2") (pin "7") (pinfunction "PGND_4_7") (pintype "power_in"))
      (node (ref "U2") (pin "8") (pinfunction "PGND_5_8") (pintype "power_in"))
      (node (ref "U4") (pin "10") (pinfunction "GND_10") (pintype "bidirectional"))
      (node (ref "U5") (pin "10") (pinfunction "GND_10") (pintype "bidirectional"))
      (node (ref "U6") (pin "3") (pinfunction "P$V-_3") (pintype "bidirectional"))
      (node (ref "U7") (pin "18") (pinfunction "GND18_18") (pintype "power_in"))
      (node (ref "U7") (pin "21") (pinfunction "GND21_21") (pintype "power_in"))
      (node (ref "U7") (pin "25") (pinfunction "AGND_25") (pintype "power_in"))
      (node (ref "U7") (pin "26") (pinfunction "TEST_26") (pintype "input"))
      (node (ref "U7") (pin "7") (pinfunction "GND7_7") (pintype "power_in"))
      (node (ref "U8") (pin "7") (pinfunction "GND_7") (pintype "bidirectional"))
    )
    (net (code "15") (name "GPIB_ATN") (class "Default")
      (node (ref "PL1") (pin "11") (pinfunction "11_11") (pintype "passive"))
      (node (ref "U5") (pin "8") (pinfunction "ATN2_8") (pintype "bidirectional"))
    )
    (net (code "16") (name "GPIB_D1") (class "Default")
      (node (ref "PL1") (pin "1") (pinfunction "1_1") (pintype "passive"))
      (node (ref "U2") (pin "23") (pinfunction "DRAIN0_23") (pintype "output"))
      (node (ref "U4") (pin "2") (pinfunction "B1_2") (pintype "bidirectional"))
    )
    (net (code "17") (name "GPIB_D2") (class "Default")
      (node (ref "PL1") (pin "2") (pinfunction "2_2") (pintype "passive"))
      (node (ref "U2") (pin "24") (pinfunction "DRAIN1_24") (pintype "output"))
      (node (ref "U4") (pin "3") (pinfunction "B2_3") (pintype "bidirectional"))
    )
    (net (code "18") (name "GPIB_D3") (class "Default")
      (node (ref "PL1") (pin "3") (pinfunction "3_3") (pintype "passive"))
      (node (ref "U2") (pin "1") (pinfunction "DRAIN2_1") (pintype "output"))
      (node (ref "U4") (pin "4") (pinfunction "B3_4") (pintype "bidirectional"))
    )
    (net (code "19") (name "GPIB_D4") (class "Default")
      (node (ref "PL1") (pin "4") (pinfunction "4_4") (pintype "passive"))
      (node (ref "U2") (pin "2") (pinfunction "DRAIN3_2") (pintype "output"))
      (node (ref "U4") (pin "5") (pinfunction "B4_5") (pintype "bidirectional"))
    )
    (net (code "20") (name "GPIB_D5") (class "Default")
      (node (ref "PL1") (pin "13") (pinfunction "13_13") (pintype "passive"))
      (node (ref "U2") (pin "11") (pinfunction "DRAIN4_11") (pintype "output"))
      (node (ref "U4") (pin "6") (pinfunction "B5_6") (pintype "bidirectional"))
    )
    (net (code "21") (name "GPIB_D6") (class "Default")
      (node (ref "PL1") (pin "14") (pinfunction "14_14") (pintype "passive"))
      (node (ref "U2") (pin "12") (pinfunction "DRAIN5_12") (pintype "output"))
      (node (ref "U4") (pin "7") (pinfunction "B6_7") (pintype "bidirectional"))
    )
    (net (code "22") (name "GPIB_D7") (class "Default")
      (node (ref "PL1") (pin "15") (pinfunction "15_15") (pintype "passive"))
      (node (ref "U2") (pin "13") (pinfunction "DRAIN6_13") (pintype "output"))
      (node (ref "U4") (pin "8") (pinfunction "B7_8") (pintype "bidirectional"))
    )
    (net (code "23") (name "GPIB_D8") (class "Default")
      (node (ref "PL1") (pin "16") (pinfunction "16_16") (pintype "passive"))
      (node (ref "U2") (pin "14") (pinfunction "DRAIN7_14") (pintype "output"))
      (node (ref "U4") (pin "9") (pinfunction "B8_9") (pintype "bidirectional"))
    )
    (net (code "24") (name "GPIB_DAV") (class "Default")
      (node (ref "PL1") (pin "6") (pinfunction "6_6") (pintype "passive"))
      (node (ref "U5") (pin "6") (pinfunction "DAV2_6") (pintype "bidirectional"))
    )
    (net (code "25") (name "GPIB_EOI") (class "Default")
      (node (ref "PL1") (pin "5") (pinfunction "5_5") (pintype "passive"))
      (node (ref "U5") (pin "7") (pinfunction "EOI2_7") (pintype "bidirectional"))
    )
    (net (code "26") (name "GPIB_IFC") (class "Default")
      (node (ref "PL1") (pin "9") (pinfunction "9_9") (pintype "passive"))
      (node (ref "U5") (pin "3") (pinfunction "IFC2_3") (pintype "bidirectional"))
    )
    (net (code "27") (name "GPIB_NDAC") (class "Default")
      (node (ref "PL1") (pin "8") (pinfunction "8_8") (pintype "passive"))
      (node (ref "U5") (pin "4") (pinfunction "NDAC2_4") (pintype "bidirectional"))
    )
    (net (code "28") (name "GPIB_NRFD") (class "Default")
      (node (ref "PL1") (pin "7") (pinfunction "7_7") (pintype "passive"))
      (node (ref "U5") (pin "5") (pinfunction "NRFD2_5") (pintype "bidirectional"))
    )
    (net (code "29") (name "GPIB_REN") (class "Default")
      (node (ref "PL1") (pin "17") (pinfunction "17_17") (pintype "passive"))
      (node (ref "U5") (pin "2") (pinfunction "REN2_2") (pintype "bidirectional"))
    )
    (net (code "30") (name "GPIB_SRQ") (class "Default")
      (node (ref "PL1") (pin "10") (pinfunction "10_10") (pintype "passive"))
      (node (ref "U5") (pin "9") (pinfunction "SRQ2_9") (pintype "bidirectional"))
    )
    (net (code "31") (name "HC595_RCLK") (class "Default")
      (node (ref "U1") (pin "42") (pinfunction "PB2(AIN0/INT2)_42") (pintype "bidirectional"))
      (node (ref "U2") (pin "9") (pinfunction "RCK_9") (pintype "input"))
    )
    (net (code "32") (name "MISO") (class "Default")
      (node (ref "J2") (pin "1") (pinfunction "1_1") (pintype "bidirectional"))
      (node (ref "R55") (pin "2") (pinfunction "2_2") (pintype "passive"))
      (node (ref "U1") (pin "2") (pinfunction "PB6(0C3A/MISO)_2") (pintype "bidirectional"))
    )
    (net (code "33") (name "MISO_5V") (class "Default")
      (node (ref "R55") (pin "1") (pinfunction "1_1") (pintype "passive"))
      (node (ref "U8") (pin "13") (pinfunction "B1_13") (pintype "bidirectional"))
    )
    (net (code "34") (name "MOSI") (class "Default")
      (node (ref "J2") (pin "4") (pinfunction "4_4") (pintype "bidirectional"))
      (node (ref "R57") (pin "2") (pinfunction "2_2") (pintype "passive"))
      (node (ref "U1") (pin "1") (pinfunction "PB5(ICP3/MOSI)_1") (pintype "bidirectional"))
      (node (ref "U2") (pin "22") (pinfunction "SERIN_22") (pintype "input"))
    )
    (net (code "35") (name "MOSI_5V0") (class "Default")
      (node (ref "R57") (pin "1") (pinfunction "1_1") (pintype "passive"))
      (node (ref "U8") (pin "11") (pinfunction "B3_11") (pintype "bidirectional"))
    )
    (net (code "36") (name "NRESET") (class "Default")
      (node (ref "J2") (pin "5") (pinfunction "5_5") (pintype "bidirectional"))
      (node (ref "R7") (pin "1") (pinfunction "1_1") (pintype "passive"))
      (node (ref "U1") (pin "4") (pinfunction "~{RESET}_4") (pintype "bidirectional"))
    )
    (net (code "37") (name "Net-(C11-Pad1)") (class "Default")
      (node (ref "C11") (pin "1") (pinfunction "1_1") (pintype "passive"))
      (node (ref "F2") (pin "1") (pinfunction "1_1") (pintype "bidirectional"))
      (node (ref "J4") (pin "VBUS") (pinfunction "VBUS_VBUS") (pintype "power_in"))
    )
    (net (code "38") (name "Net-(J1-PWR)") (class "Default")
      (node (ref "D2") (pin "A") (pinfunction "A_A") (pintype "passive"))
      (node (ref "J1") (pin "VIN0") (pinfunction "PWR_VIN0") (pintype "bidirectional"))
    )
    (net (code "39") (name "Net-(LED1-PadA)") (class "Default")
      (node (ref "LED1") (pin "A") (pinfunction "A_A") (pintype "passive"))
      (node (ref "R2") (pin "2") (pinfunction "2_2") (pintype "passive"))
    )
    (net (code "40") (name "Net-(LED2-PadA)") (class "Default")
      (node (ref "LED2") (pin "A") (pinfunction "A_A") (pintype "passive"))
      (node (ref "R53") (pin "2") (pinfunction "2_2") (pintype "passive"))
    )
    (net (code "41") (name "Net-(LED3-PadA)") (class "Default")
      (node (ref "LED3") (pin "A") (pinfunction "A_A") (pintype "passive"))
      (node (ref "R23") (pin "1") (pinfunction "1_1") (pintype "passive"))
    )
    (net (code "42") (name "Net-(LED4-PadA)") (class "Default")
      (node (ref "LED4") (pin "A") (pinfunction "A_A") (pintype "passive"))
      (node (ref "R24") (pin "1") (pinfunction "1_1") (pintype "passive"))
    )
    (net (code "43") (name "Net-(LED5-PadA)") (class "Default")
      (node (ref "LED5") (pin "A") (pinfunction "A_A") (pintype "passive"))
      (node (ref "R6") (pin "2") (pinfunction "2_2") (pintype "passive"))
    )
    (net (code "44") (name "Net-(LED6-PadA)") (class "Default")
      (node (ref "LED6") (pin "A") (pinfunction "A_A") (pintype "passive"))
      (node (ref "R52") (pin "2") (pinfunction "2_2") (pintype "passive"))
    )
    (net (code "45") (name "Net-(U1-PC0(SCL))") (class "Default")
      (node (ref "R2") (pin "1") (pinfunction "1_1") (pintype "passive"))
      (node (ref "U1") (pin "19") (pinfunction "PC0(SCL)_19") (pintype "bidirectional"))
    )
    (net (code "46") (name "Net-(U1-PC1(SDA))") (class "Default")
      (node (ref "R53") (pin "1") (pinfunction "1_1") (pintype "passive"))
      (node (ref "U1") (pin "20") (pinfunction "PC1(SDA)_20") (pintype "bidirectional"))
    )
    (net (code "47") (name "Net-(U1-XTAL1)") (class "Default")
      (node (ref "C4") (pin "2") (pinfunction "2_2") (pintype "passive"))
      (node (ref "U1") (pin "8") (pinfunction "XTAL1_8") (pintype "bidirectional"))
      (node (ref "Y2") (pin "3") (pinfunction "2_3") (pintype "passive"))
    )
    (net (code "48") (name "Net-(U1-XTAL2)") (class "Default")
      (node (ref "C3") (pin "2") (pinfunction "2_2") (pintype "passive"))
      (node (ref "U1") (pin "7") (pinfunction "XTAL2_7") (pintype "bidirectional"))
      (node (ref "Y2") (pin "1") (pinfunction "1_1") (pintype "passive"))
    )
    (net (code "49") (name "Net-(U2-~{G})") (class "Default")
      (node (ref "U2") (pin "4") (pinfunction "~{G}_4") (pintype "input"))
      (node (ref "U6") (pin "4") (pinfunction "Y_4") (pintype "bidirectional"))
    )
    (net (code "50") (name "Net-(U9-ADJ)") (class "Default")
      (node (ref "R1") (pin "2") (pinfunction "2_2") (pintype "passive"))
      (node (ref "R49") (pin "1") (pinfunction "1_1") (pintype "passive"))
      (node (ref "U9") (pin "1") (pinfunction "ADJ_1") (pintype "input"))
    )
    (net (code "51") (name "Net-(U11-~{MR})") (class "Default")
      (node (ref "S1") (pin "3") (pinfunction "3_3") (pintype "passive"))
      (node (ref "S1") (pin "4") (pinfunction "4_4") (pintype "passive"))
      (node (ref "U11") (pin "3") (pinfunction "~{MR}_3") (pintype "input"))
    )
    (net (code "52") (name "Net-(U11-~{RESET})") (class "Default")
      (node (ref "R3") (pin "1") (pinfunction "1_1") (pintype "passive"))
      (node (ref "R7") (pin "2") (pinfunction "2_2") (pintype "passive"))
      (node (ref "U11") (pin "2") (pinfunction "~{RESET}_2") (pintype "output"))
    )
    (net (code "53") (name "PA0") (class "Default")
      (node (ref "R8") (pin "2") (pinfunction "2_2") (pintype "passive"))
      (node (ref "U1") (pin "37") (pinfunction "PA0(ADC0/PCINT0)_37") (pintype "bidirectional"))
    )
    (net (code "54") (name "PA0_D1") (class "Default")
      (node (ref "R8") (pin "1") (pinfunction "1_1") (pintype "passive"))
      (node (ref "U4") (pin "19") (pinfunction "D1_19") (pintype "bidirectional"))
    )
    (net (code "55") (name "PA1") (class "Default")
      (node (ref "R9") (pin "2") (pinfunction "2_2") (pintype "passive"))
      (node (ref "U1") (pin "36") (pinfunction "PA1(ADC1/PCINT1)_36") (pintype "bidirectional"))
    )
    (net (code "56") (name "PA1_D2") (class "Default")
      (node (ref "R9") (pin "1") (pinfunction "1_1") (pintype "passive"))
      (node (ref "U4") (pin "18") (pinfunction "D2_18") (pintype "bidirectional"))
    )
    (net (code "57") (name "PA2") (class "Default")
      (node (ref "R10") (pin "2") (pinfunction "2_2") (pintype "passive"))
      (node (ref "U1") (pin "35") (pinfunction "PA2(ADC2/PCINT2)_35") (pintype "bidirectional"))
    )
    (net (code "58") (name "PA2_D3") (class "Default")
      (node (ref "R10") (pin "1") (pinfunction "1_1") (pintype "passive"))
      (node (ref "U4") (pin "17") (pinfunction "D3_17") (pintype "bidirectional"))
    )
    (net (code "59") (name "PA3") (class "Default")
      (node (ref "R11") (pin "2") (pinfunction "2_2") (pintype "passive"))
      (node (ref "U1") (pin "34") (pinfunction "PA3(ADC3/PCINT3)_34") (pintype "bidirectional"))
    )
    (net (code "60") (name "PA3_D4") (class "Default")
      (node (ref "R11") (pin "1") (pinfunction "1_1") (pintype "passive"))
      (node (ref "U4") (pin "16") (pinfunction "D4_16") (pintype "bidirectional"))
    )
    (net (code "61") (name "PA4") (class "Default")
      (node (ref "R13") (pin "2") (pinfunction "2_2") (pintype "passive"))
      (node (ref "U1") (pin "33") (pinfunction "PA4(ADC4/PCINT4)_33") (pintype "bidirectional"))
    )
    (net (code "62") (name "PA4_D5") (class "Default")
      (node (ref "R13") (pin "1") (pinfunction "1_1") (pintype "passive"))
      (node (ref "U4") (pin "15") (pinfunction "D5_15") (pintype "bidirectional"))
    )
    (net (code "63") (name "PA5") (class "Default")
      (node (ref "R25") (pin "2") (pinfunction "2_2") (pintype "passive"))
      (node (ref "U1") (pin "32") (pinfunction "PA5(ADC5/PCINT5)_32") (pintype "bidirectional"))
    )
    (net (code "64") (name "PA5_D6") (class "Default")
      (node (ref "R25") (pin "1") (pinfunction "1_1") (pintype "passive"))
      (node (ref "U4") (pin "14") (pinfunction "D6_14") (pintype "bidirectional"))
    )
    (net (code "65") (name "PA6") (class "Default")
      (node (ref "R26") (pin "2") (pinfunction "2_2") (pintype "passive"))
      (node (ref "U1") (pin "31") (pinfunction "PA6(ADC6/PCINT6)_31") (pintype "bidirectional"))
    )
    (net (code "66") (name "PA6_D7") (class "Default")
      (node (ref "R26") (pin "1") (pinfunction "1_1") (pintype "passive"))
      (node (ref "U4") (pin "13") (pinfunction "D7_13") (pintype "bidirectional"))
    )
    (net (code "67") (name "PA7") (class "Default")
      (node (ref "R27") (pin "2") (pinfunction "2_2") (pintype "passive"))
      (node (ref "U1") (pin "30") (pinfunction "PA7(ADC7/PCINT7)_30") (pintype "bidirectional"))
    )
    (net (code "68") (name "PA7_D8") (class "Default")
      (node (ref "R27") (pin "1") (pinfunction "1_1") (pintype "passive"))
      (node (ref "U4") (pin "12") (pinfunction "D8_12") (pintype "bidirectional"))
    )
    (net (code "69") (name "PB0_EOI") (class "Default")
      (node (ref "U1") (pin "40") (pinfunction "PB0(XCKO/T0/PCINT8)_40") (pintype "bidirectional"))
      (node (ref "U5") (pin "14") (pinfunction "EOI_14") (pintype "bidirectional"))
      (node (ref "U6") (pin "1") (pinfunction "A_1") (pintype "bidirectional"))
    )
    (net (code "70") (name "PB1_DAV") (class "Default")
      (node (ref "U1") (pin "41") (pinfunction "PB1(T1/CLK0/PCINT9)_41") (pintype "bidirectional"))
      (node (ref "U5") (pin "15") (pinfunction "DAV_15") (pintype "bidirectional"))
    )
    (net (code "71") (name "PB3_CS") (class "Default")
      (node (ref "R58") (pin "2") (pinfunction "2_2") (pintype "passive"))
      (node (ref "U1") (pin "43") (pinfunction "PB3(AIN1/OC0A)_43") (pintype "bidirectional"))
      (node (ref "U8") (pin "10") (pinfunction "B4_10") (pintype "bidirectional"))
    )
    (net (code "72") (name "PB4_CD") (class "Default")
      (node (ref "R54") (pin "2") (pinfunction "2_2") (pintype "passive"))
      (node (ref "U1") (pin "44") (pinfunction "PB4(SS/OC0B)_44") (pintype "bidirectional"))
    )
    (net (code "73") (name "PD2_NRFD") (class "Default")
      (node (ref "U1") (pin "11") (pinfunction "PD2(RXD1/INT0)_11") (pintype "bidirectional"))
      (node (ref "U5") (pin "16") (pinfunction "NRFD_16") (pintype "bidirectional"))
    )
    (net (code "74") (name "PD3_NDAC") (class "Default")
      (node (ref "U1") (pin "12") (pinfunction "PD3(TXD1/INT1)_12") (pintype "bidirectional"))
      (node (ref "U5") (pin "17") (pinfunction "NDAC_17") (pintype "bidirectional"))
    )
    (net (code "75") (name "PD4_IFC") (class "Default")
      (node (ref "U1") (pin "13") (pinfunction "PD4(XCK1/OC1B)_13") (pintype "bidirectional"))
      (node (ref "U2") (pin "3") (pinfunction "~{SRCLR}_3") (pintype "input"))
      (node (ref "U5") (pin "18") (pinfunction "IFC_18") (pintype "bidirectional"))
    )
    (net (code "76") (name "PD5_SRQ") (class "Default")
      (node (ref "U1") (pin "14") (pinfunction "PD5(OC1A)_14") (pintype "bidirectional"))
      (node (ref "U5") (pin "12") (pinfunction "SRQ_12") (pintype "bidirectional"))
    )
    (net (code "77") (name "PD6_ATN") (class "Default")
      (node (ref "U1") (pin "15") (pinfunction "PD6(OC2B/ICP)_15") (pintype "bidirectional"))
      (node (ref "U5") (pin "13") (pinfunction "ATN_13") (pintype "bidirectional"))
      (node (ref "U6") (pin "2") (pinfunction "B_2") (pintype "bidirectional"))
    )
    (net (code "78") (name "PD7_REN") (class "Default")
      (node (ref "U1") (pin "16") (pinfunction "PD7(OC2A)_16") (pintype "bidirectional"))
      (node (ref "U5") (pin "19") (pinfunction "REN_19") (pintype "bidirectional"))
    )
    (net (code "79") (name "PE") (class "Default")
      (node (ref "J9") (pin "2") (pinfunction "2_2") (pintype "passive"))
      (node (ref "U1") (pin "22") (pinfunction "PC3(TMS)_22") (pintype "bidirectional"))
      (node (ref "U4") (pin "11") (pinfunction "PE_11") (pintype "input"))
    )
    (net (code "80") (name "RXD") (class "Default")
      (node (ref "R19") (pin "1") (pinfunction "1_1") (pintype "passive"))
      (node (ref "U1") (pin "9") (pinfunction "PD0(RXD0/T3*)_9") (pintype "bidirectional"))
    )
    (net (code "81") (name "RXLED") (class "Default")
      (node (ref "LED5") (pin "C") (pinfunction "C_C") (pintype "passive"))
      (node (ref "U7") (pin "22") (pinfunction "RXLED_22") (pintype "input"))
    )
    (net (code "82") (name "SCK") (class "Default")
      (node (ref "J2") (pin "3") (pinfunction "3_3") (pintype "bidirectional"))
      (node (ref "R56") (pin "2") (pinfunction "2_2") (pintype "passive"))
      (node (ref "U1") (pin "3") (pinfunction "PB7(OC3B/SCK)_3") (pintype "bidirectional"))
      (node (ref "U2") (pin "10") (pinfunction "SRCK_10") (pintype "input"))
    )
    (net (code "83") (name "SD_CD") (class "Default")
      (node (ref "J3") (pin "CD") (pinfunction "CD_CD") (pintype "bidirectional"))
      (node (ref "R12") (pin "1") (pinfunction "1_1") (pintype "passive"))
      (node (ref "R54") (pin "1") (pinfunction "1_1") (pintype "passive"))
    )
    (net (code "84") (name "SD_CLK") (class "Default")
      (node (ref "J3") (pin "5") (pinfunction "CLK_5") (pintype "bidirectional"))
      (node (ref "U8") (pin "3") (pinfunction "A2_3") (pintype "bidirectional"))
    )
    (net (code "85") (name "SD_CS") (class "Default")
      (node (ref "J3") (pin "1") (pinfunction "CD/DAT3_1") (pintype "bidirectional"))
      (node (ref "U8") (pin "5") (pinfunction "A4_5") (pintype "bidirectional"))
    )
    (net (code "86") (name "SD_DAT1") (class "Default")
      (node (ref "J3") (pin "8") (pinfunction "DAT1_8") (pintype "bidirectional"))
      (node (ref "R16") (pin "1") (pinfunction "1_1") (pintype "passive"))
    )
    (net (code "87") (name "SD_DAT2") (class "Default")
      (node (ref "J3") (pin "9") (pinfunction "DAT2_9") (pintype "bidirectional"))
      (node (ref "R17") (pin "1") (pinfunction "1_1") (pintype "passive"))
    )
    (net (code "88") (name "SD_MISO") (class "Default")
      (node (ref "J3") (pin "7") (pinfunction "DAT0_7") (pintype "bidirectional"))
      (node (ref "R18") (pin "1") (pinfunction "1_1") (pintype "passive"))
      (node (ref "U8") (pin "2") (pinfunction "A1_2") (pintype "bidirectional"))
    )
    (net (code "89") (name "SD_MOSI") (class "Default")
      (node (ref "J3") (pin "2") (pinfunction "CMD_2") (pintype "bidirectional"))
      (node (ref "U8") (pin "4") (pinfunction "A3_4") (pintype "bidirectional"))
    )
    (net (code "90") (name "SD_WP") (class "Default")
      (node (ref "J3") (pin "WP") (pinfunction "WP_WP") (pintype "bidirectional"))
      (node (ref "R59") (pin "2") (pinfunction "2_2") (pintype "passive"))
      (node (ref "R60") (pin "1") (pinfunction "1_1") (pintype "passive"))
    )
    (net (code "91") (name "TE") (class "Default")
      (node (ref "J9") (pin "1") (pinfunction "1_1") (pintype "passive"))
      (node (ref "R5") (pin "1") (pinfunction "1_1") (pintype "passive"))
      (node (ref "U1") (pin "21") (pinfunction "PC2(TCK)_21") (pintype "bidirectional"))
      (node (ref "U4") (pin "1") (pinfunction "TE_1") (pintype "input"))
      (node (ref "U5") (pin "1") (pinfunction "TE_1") (pintype "input"))
    )
    (net (code "92") (name "TXD") (class "Default")
      (node (ref "R20") (pin "1") (pinfunction "1_1") (pintype "passive"))
      (node (ref "U1") (pin "10") (pinfunction "PD1(TXD0)_10") (pintype "bidirectional"))
    )
    (net (code "93") (name "TXLED") (class "Default")
      (node (ref "LED6") (pin "C") (pinfunction "C_C") (pintype "passive"))
      (node (ref "U7") (pin "23") (pinfunction "TXLED_23") (pintype "input"))
    )
    (net (code "94") (name "USBVCC") (class "Default")
      (node (ref "C16") (pin "1") (pinfunction "1_1") (pintype "passive"))
      (node (ref "C17") (pin "+") (pinfunction "+_+") (pintype "passive"))
      (node (ref "F2") (pin "2") (pinfunction "2_2") (pintype "bidirectional"))
      (node (ref "U7") (pin "20") (pinfunction "VCC_20") (pintype "power_in"))
    )
    (net (code "95") (name "VIN") (class "Default")
      (node (ref "C14") (pin "+") (pinfunction "+_+") (pintype "passive"))
      (node (ref "D2") (pin "C") (pinfunction "C_C") (pintype "passive"))
      (node (ref "J5") (pin "1") (pinfunction "1_1") (pintype "passive"))
      (node (ref "U9") (pin "3") (pinfunction "IN_3") (pintype "input"))
    )
    (net (code "96") (name "unconnected-(J4-PadID)") (class "Default")
      (node (ref "J4") (pin "ID") (pinfunction "ID_ID") (pintype "bidirectional"))
    )
    (net (code "97") (name "unconnected-(U1-PC5(TDI)-Pad24)") (class "Default")
      (node (ref "U1") (pin "24") (pinfunction "PC5(TDI)_24") (pintype "bidirectional"))
    )
    (net (code "98") (name "unconnected-(U1-PC6(TOSC1)-Pad25)") (class "Default")
      (node (ref "U1") (pin "25") (pinfunction "PC6(TOSC1)_25") (pintype "bidirectional"))
    )
    (net (code "99") (name "unconnected-(U1-PC7(TOSC2)-Pad26)") (class "Default")
      (node (ref "U1") (pin "26") (pinfunction "PC7(TOSC2)_26") (pintype "bidirectional"))
    )
    (net (code "100") (name "unconnected-(U2-SEROUT-Pad15)") (class "Default")
      (node (ref "U2") (pin "15") (pinfunction "SEROUT_15") (pintype "output"))
    )
    (net (code "101") (name "unconnected-(U7-CTS-Pad11)") (class "Default")
      (node (ref "U7") (pin "11") (pinfunction "CTS_11") (pintype "input"))
    )
    (net (code "102") (name "unconnected-(U7-DCD-Pad10)") (class "Default")
      (node (ref "U7") (pin "10") (pinfunction "DCD_10") (pintype "input"))
    )
    (net (code "103") (name "unconnected-(U7-DSR-Pad9)") (class "Default")
      (node (ref "U7") (pin "9") (pinfunction "DSR_9") (pintype "input"))
    )
    (net (code "104") (name "unconnected-(U7-DTR-Pad2)") (class "Default")
      (node (ref "U7") (pin "2") (pinfunction "DTR_2") (pintype "output"))
    )
    (net (code "105") (name "unconnected-(U7-OSCI-Pad27)") (class "Default")
      (node (ref "U7") (pin "27") (pinfunction "OSCI_27") (pintype "input"))
    )
    (net (code "106") (name "unconnected-(U7-OSCO-Pad28)") (class "Default")
      (node (ref "U7") (pin "28") (pinfunction "OSCO_28") (pintype "output"))
    )
    (net (code "107") (name "unconnected-(U7-PWREN-Pad14)") (class "Default")
      (node (ref "U7") (pin "14") (pinfunction "PWREN_14") (pintype "input"))
    )
    (net (code "108") (name "unconnected-(U7-RESET-Pad19)") (class "Default")
      (node (ref "U7") (pin "19") (pinfunction "RESET_19") (pintype "input"))
    )
    (net (code "109") (name "unconnected-(U7-RI-Pad6)") (class "Default")
      (node (ref "U7") (pin "6") (pinfunction "RI_6") (pintype "input"))
    )
    (net (code "110") (name "unconnected-(U7-RTS-Pad3)") (class "Default")
      (node (ref "U7") (pin "3") (pinfunction "RTS_3") (pintype "output"))
    )
    (net (code "111") (name "unconnected-(U7-SLEEP-Pad12)") (class "Default")
      (node (ref "U7") (pin "12") (pinfunction "SLEEP_12") (pintype "input"))
    )
    (net (code "112") (name "unconnected-(U7-TXDEN-Pad13)") (class "Default")
      (node (ref "U7") (pin "13") (pinfunction "TXDEN_13") (pintype "input"))
    )
    (net (code "113") (name "unconnected-(U10-BP-Pad4)") (class "Default")
      (node (ref "U10") (pin "4") (pinfunction "BP_4") (pintype "input"))
    )
  )
)
